# ioboard.net
KiCad netlist of a schematic drawn in EAGLE
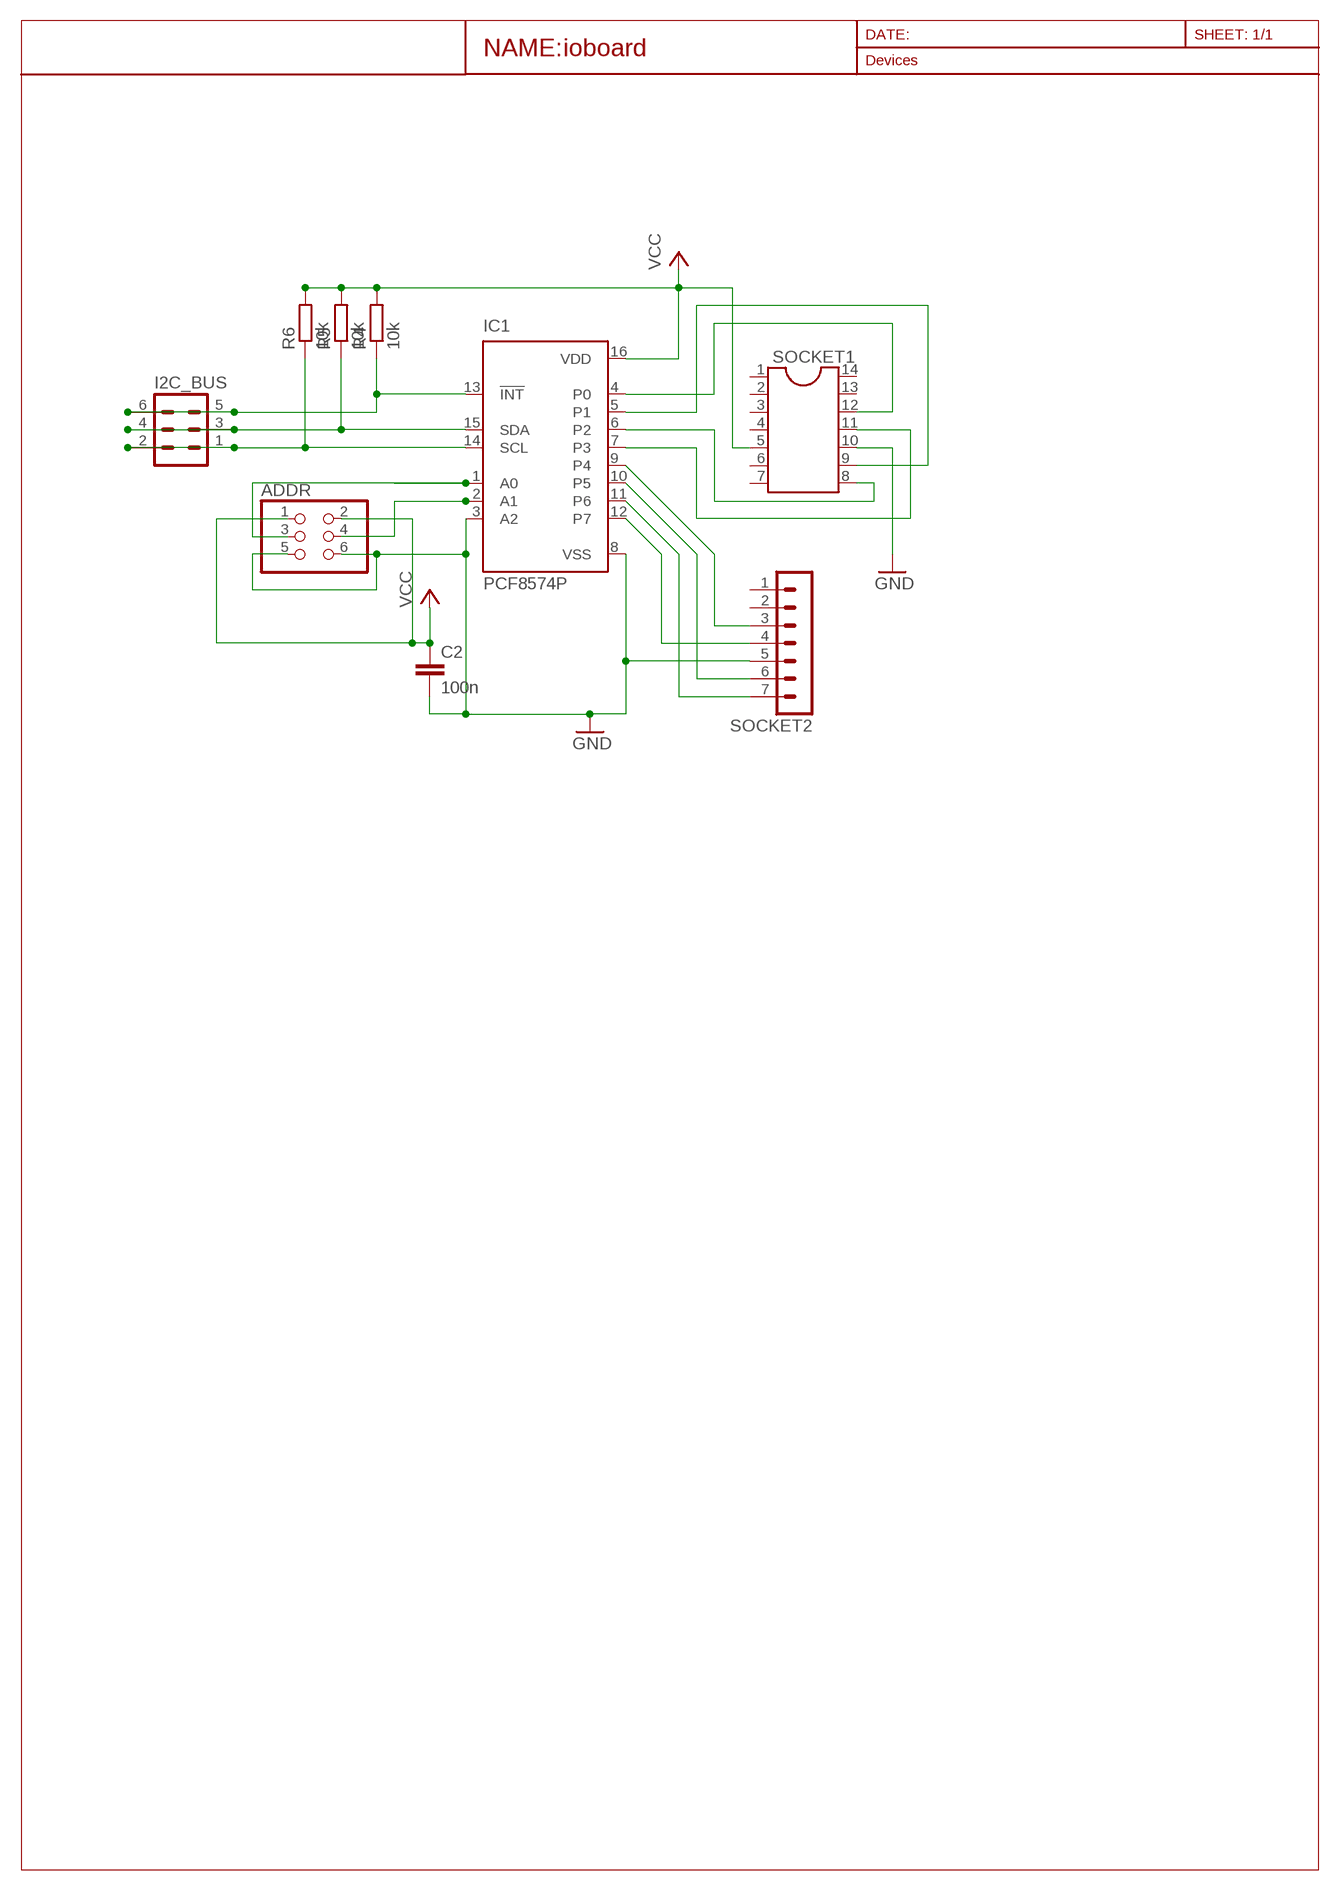
[diagram p0: schematic, sheet 1]

(export (version "E")
  (design (tool "Eeschema 10.0.6"))
  (components
    (comp (ref "ADDR")
      (value "PINHD-2X3")
      (footprint "eagle-import:2X03")
      (libsource (lib "eagle-import") (part "PINHD-2X3"))
    )
    (comp (ref "C2")
      (value "100n")
      (footprint "eagle-import:C050-024X044")
      (libsource (lib "eagle-import") (part "C-EU050-024X044"))
    )
    (comp (ref "I2C_BUS")
      (value "MA03-2")
      (footprint "eagle-import:MA03-2")
      (libsource (lib "eagle-import") (part "MA03-2"))
    )
    (comp (ref "IC1")
      (value "PCF8574P")
      (footprint "eagle-import:DIL16")
      (fields (field (name "MPN") "PCF8574PN"))
      (libsource (lib "eagle-import") (part "PCF8574P"))
    )
    (comp (ref "R4")
      (value "10k")
      (footprint "eagle-import:0207_10")
      (libsource (lib "eagle-import") (part "R-EU_0207/10"))
    )
    (comp (ref "R5")
      (value "10k")
      (footprint "eagle-import:0207_10")
      (libsource (lib "eagle-import") (part "R-EU_0207/10"))
    )
    (comp (ref "R6")
      (value "10k")
      (footprint "eagle-import:0207_10")
      (libsource (lib "eagle-import") (part "R-EU_0207/10"))
    )
    (comp (ref "SOCKET1")
      (value "DIL14S")
      (footprint "eagle-import:SOCKET-14")
      (libsource (lib "eagle-import") (part "DIL14S"))
    )
    (comp (ref "SOCKET2")
      (value "MA07-1")
      (footprint "eagle-import:MA07-1")
      (libsource (lib "eagle-import") (part "MA07-1"))
    )
  )
  (nets
    (net (code "1") (name "GND") (class "Default")
      (node (ref "ADDR") (pin "5") (pinfunction "5_5") (pintype "passive"))
      (node (ref "ADDR") (pin "6") (pinfunction "6_6") (pintype "passive"))
      (node (ref "C2") (pin "2") (pinfunction "2_2") (pintype "passive"))
      (node (ref "IC1") (pin "3") (pinfunction "A2_3") (pintype "input"))
      (node (ref "IC1") (pin "8") (pinfunction "VSS_8") (pintype "power_in"))
      (node (ref "SOCKET1") (pin "10") (pinfunction "10_10") (pintype "passive"))
      (node (ref "SOCKET2") (pin "5") (pinfunction "5_5") (pintype "passive"))
    )
    (net (code "2") (name "Net-(IC1-A0)") (class "Default")
      (node (ref "ADDR") (pin "3") (pinfunction "3_3") (pintype "passive"))
      (node (ref "IC1") (pin "1") (pinfunction "A0_1") (pintype "input"))
    )
    (net (code "3") (name "Net-(IC1-A1)") (class "Default")
      (node (ref "ADDR") (pin "4") (pinfunction "4_4") (pintype "passive"))
      (node (ref "IC1") (pin "2") (pinfunction "A1_2") (pintype "input"))
    )
    (net (code "4") (name "Net-(IC1-P0)") (class "Default")
      (node (ref "IC1") (pin "4") (pinfunction "P0_4") (pintype "bidirectional"))
      (node (ref "SOCKET1") (pin "12") (pinfunction "12_12") (pintype "passive"))
    )
    (net (code "5") (name "Net-(IC1-P1)") (class "Default")
      (node (ref "IC1") (pin "5") (pinfunction "P1_5") (pintype "bidirectional"))
      (node (ref "SOCKET1") (pin "9") (pinfunction "9_9") (pintype "passive"))
    )
    (net (code "6") (name "Net-(IC1-P2)") (class "Default")
      (node (ref "IC1") (pin "6") (pinfunction "P2_6") (pintype "bidirectional"))
      (node (ref "SOCKET1") (pin "8") (pinfunction "8_8") (pintype "passive"))
    )
    (net (code "7") (name "Net-(IC1-P3)") (class "Default")
      (node (ref "IC1") (pin "7") (pinfunction "P3_7") (pintype "bidirectional"))
      (node (ref "SOCKET1") (pin "11") (pinfunction "11_11") (pintype "passive"))
    )
    (net (code "8") (name "Net-(IC1-P4)") (class "Default")
      (node (ref "IC1") (pin "9") (pinfunction "P4_9") (pintype "bidirectional"))
      (node (ref "SOCKET2") (pin "3") (pinfunction "3_3") (pintype "passive"))
    )
    (net (code "9") (name "Net-(IC1-P5)") (class "Default")
      (node (ref "IC1") (pin "10") (pinfunction "P5_10") (pintype "bidirectional"))
      (node (ref "SOCKET2") (pin "6") (pinfunction "6_6") (pintype "passive"))
    )
    (net (code "10") (name "Net-(IC1-P6)") (class "Default")
      (node (ref "IC1") (pin "11") (pinfunction "P6_11") (pintype "bidirectional"))
      (node (ref "SOCKET2") (pin "7") (pinfunction "7_7") (pintype "passive"))
    )
    (net (code "11") (name "Net-(IC1-P7)") (class "Default")
      (node (ref "IC1") (pin "12") (pinfunction "P7_12") (pintype "bidirectional"))
      (node (ref "SOCKET2") (pin "4") (pinfunction "4_4") (pintype "passive"))
    )
    (net (code "12") (name "Net-(IC1-SCL)") (class "Default")
      (node (ref "I2C_BUS") (pin "1") (pinfunction "1_1") (pintype "passive"))
      (node (ref "I2C_BUS") (pin "2") (pinfunction "2_2") (pintype "passive"))
      (node (ref "IC1") (pin "14") (pinfunction "SCL_14") (pintype "input"))
      (node (ref "R6") (pin "1") (pinfunction "1_1") (pintype "passive"))
    )
    (net (code "13") (name "Net-(IC1-SDA)") (class "Default")
      (node (ref "I2C_BUS") (pin "3") (pinfunction "3_3") (pintype "passive"))
      (node (ref "I2C_BUS") (pin "4") (pinfunction "4_4") (pintype "passive"))
      (node (ref "IC1") (pin "15") (pinfunction "SDA_15") (pintype "bidirectional"))
      (node (ref "R5") (pin "1") (pinfunction "1_1") (pintype "passive"))
    )
    (net (code "14") (name "Net-(IC1-~{INT})") (class "Default")
      (node (ref "I2C_BUS") (pin "5") (pinfunction "5_5") (pintype "passive"))
      (node (ref "I2C_BUS") (pin "6") (pinfunction "6_6") (pintype "passive"))
      (node (ref "IC1") (pin "13") (pinfunction "~{INT}_13") (pintype "output"))
      (node (ref "R4") (pin "1") (pinfunction "1_1") (pintype "passive"))
    )
    (net (code "15") (name "VCC") (class "Default")
      (node (ref "ADDR") (pin "1") (pinfunction "1_1") (pintype "passive"))
      (node (ref "ADDR") (pin "2") (pinfunction "2_2") (pintype "passive"))
      (node (ref "C2") (pin "1") (pinfunction "1_1") (pintype "passive"))
      (node (ref "IC1") (pin "16") (pinfunction "VDD_16") (pintype "power_in"))
      (node (ref "R4") (pin "2") (pinfunction "2_2") (pintype "passive"))
      (node (ref "R5") (pin "2") (pinfunction "2_2") (pintype "passive"))
      (node (ref "R6") (pin "2") (pinfunction "2_2") (pintype "passive"))
      (node (ref "SOCKET1") (pin "5") (pinfunction "5_5") (pintype "passive"))
    )
    (net (code "16") (name "unconnected-(SOCKET1-Pad1)") (class "Default")
      (node (ref "SOCKET1") (pin "1") (pinfunction "1_1") (pintype "passive"))
    )
    (net (code "17") (name "unconnected-(SOCKET1-Pad2)") (class "Default")
      (node (ref "SOCKET1") (pin "2") (pinfunction "2_2") (pintype "passive"))
    )
    (net (code "18") (name "unconnected-(SOCKET1-Pad3)") (class "Default")
      (node (ref "SOCKET1") (pin "3") (pinfunction "3_3") (pintype "passive"))
    )
    (net (code "19") (name "unconnected-(SOCKET1-Pad4)") (class "Default")
      (node (ref "SOCKET1") (pin "4") (pinfunction "4_4") (pintype "passive"))
    )
    (net (code "20") (name "unconnected-(SOCKET1-Pad6)") (class "Default")
      (node (ref "SOCKET1") (pin "6") (pinfunction "6_6") (pintype "passive"))
    )
    (net (code "21") (name "unconnected-(SOCKET1-Pad7)") (class "Default")
      (node (ref "SOCKET1") (pin "7") (pinfunction "7_7") (pintype "passive"))
    )
    (net (code "22") (name "unconnected-(SOCKET1-Pad13)") (class "Default")
      (node (ref "SOCKET1") (pin "13") (pinfunction "13_13") (pintype "passive"))
    )
    (net (code "23") (name "unconnected-(SOCKET1-Pad14)") (class "Default")
      (node (ref "SOCKET1") (pin "14") (pinfunction "14_14") (pintype "passive"))
    )
    (net (code "24") (name "unconnected-(SOCKET2-Pad1)") (class "Default")
      (node (ref "SOCKET2") (pin "1") (pinfunction "1_1") (pintype "passive"))
    )
    (net (code "25") (name "unconnected-(SOCKET2-Pad2)") (class "Default")
      (node (ref "SOCKET2") (pin "2") (pinfunction "2_2") (pintype "passive"))
    )
  )
)
